# HT62N_v1_1.net
KiCad netlist of a schematic drawn in Altium Designer
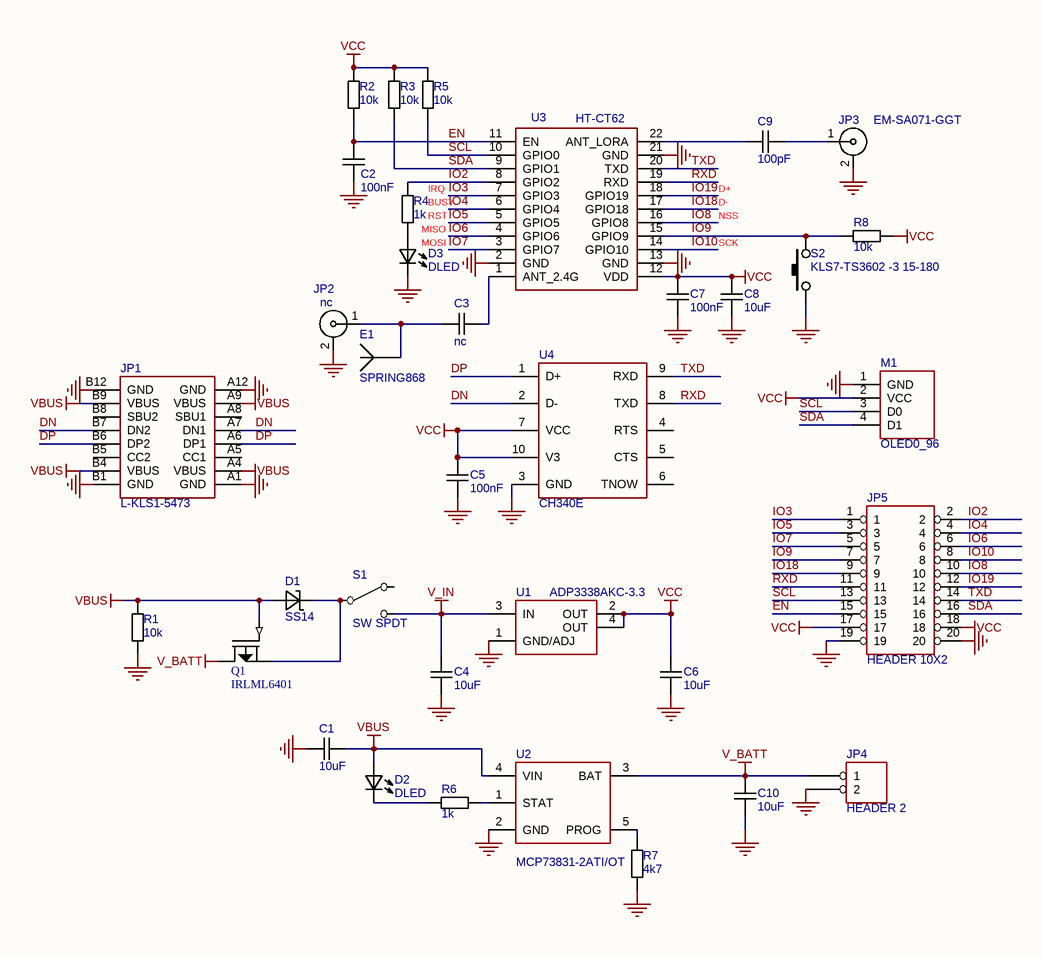
[diagram p0: HT62N_v1.1.SchDoc]

(export (version "E")
  (design (tool "Eeschema 10.0.6"))
  (components
    (comp (ref "C1")
      (value "10uF")
      (footprint "C-0805")
      (fields (field (name "VOLTAGE") "50V"))
      (libsource (lib "Passive") (part "CAPN"))
    )
    (comp (ref "C2")
      (value "100nF")
      (footprint "C-0603")
      (fields (field (name "VOLTAGE") "50V"))
      (libsource (lib "Passive") (part "CAPN"))
    )
    (comp (ref "C3")
      (value "nc")
      (footprint "C-0603")
      (fields (field (name "VOLTAGE") "50V"))
      (libsource (lib "Passive") (part "CAPN"))
    )
    (comp (ref "C4")
      (value "10uF")
      (footprint "C-0805")
      (fields (field (name "VOLTAGE") "50V"))
      (libsource (lib "Passive") (part "CAPN"))
    )
    (comp (ref "C5")
      (value "100nF")
      (footprint "C-0603")
      (fields (field (name "VOLTAGE") "50V"))
      (libsource (lib "Passive") (part "CAPN"))
    )
    (comp (ref "C6")
      (value "10uF")
      (footprint "C-0805")
      (fields (field (name "VOLTAGE") "50V"))
      (libsource (lib "Passive") (part "CAPN"))
    )
    (comp (ref "C7")
      (value "100nF")
      (footprint "C-0603")
      (fields (field (name "VOLTAGE") "50V"))
      (libsource (lib "Passive") (part "CAPN"))
    )
    (comp (ref "C8")
      (value "10uF")
      (footprint "C-0805")
      (fields (field (name "VOLTAGE") "50V"))
      (libsource (lib "Passive") (part "CAPN"))
    )
    (comp (ref "C9")
      (value "100pF")
      (footprint "C-0603")
      (fields (field (name "VOLTAGE") "50V"))
      (libsource (lib "Passive") (part "CAPN"))
    )
    (comp (ref "C10")
      (value "10uF")
      (footprint "C-0805")
      (fields (field (name "VOLTAGE") "50V"))
      (libsource (lib "Passive") (part "CAPN"))
    )
    (comp (ref "D1") (value "SS14") (footprint "D-SMA") (libsource (lib "Diodes") (part "DIODSH")))
    (comp (ref "D2") (value "DLED") (footprint "LED_3mm_RED") (libsource (lib "Diodes") (part "DLED")))
    (comp (ref "D3") (value "DLED") (footprint "LED_3mm_RED") (libsource (lib "Diodes") (part "DLED")))
    (comp (ref "E1") (value "SPRING868") (footprint "ANT_H868_V") (libsource (lib "Passive") (part "ANT")))
    (comp (ref "JP1")
      (value "L-KLS1-5473")
      (footprint "USB_C_SMD_SLOT")
      (libsource (lib "Connectors") (part "L-KLS1-5473"))
    )
    (comp (ref "JP2")
      (value "nc")
      (footprint "SMA_F_EDGE")
      (description "SMA Female R/A PCB Mount")
      (libsource (lib "Connectors") (part "SMA"))
    )
    (comp (ref "JP3")
      (value "EM-SA071-GGT")
      (footprint "SMA_F_EDGE")
      (description "SMA Female R/A PCB Mount")
      (libsource (lib "Connectors") (part "SMA"))
    )
    (comp (ref "JP4")
      (value "HEADER 2")
      (footprint "PLS1-2")
      (libsource (lib "Connectors") (part "HEADER 2"))
    )
    (comp (ref "JP5")
      (value "HEADER 10X2")
      (footprint "PLS2_10")
      (libsource (lib "Connectors") (part "HEADER 10X2"))
    )
    (comp (ref "M1")
      (value "OLED0_96")
      (footprint "OLED096_I2C")
      (libsource (lib "RFmodules") (part "OLED0_96_I2C"))
    )
    (comp (ref "Q1") (value "IRLML6401") (footprint "SOT-23") (libsource (lib "Discrete") (part "MOSF-P")))
    (comp (ref "R1") (value "10k") (footprint "R-0603") (libsource (lib "") (part "RES_2")))
    (comp (ref "R2") (value "10k") (footprint "R-0603") (libsource (lib "") (part "RES_1")))
    (comp (ref "R3") (value "10k") (footprint "R-0603") (libsource (lib "") (part "RES_1")))
    (comp (ref "R4") (value "1k") (footprint "R-0603") (libsource (lib "") (part "RES_2")))
    (comp (ref "R5") (value "10k") (footprint "R-0603") (libsource (lib "") (part "RES_1")))
    (comp (ref "R6") (value "1k") (footprint "R-0603") (libsource (lib "Passive") (part "RES")))
    (comp (ref "R7") (value "4k7") (footprint "R-0603") (libsource (lib "") (part "RES_2")))
    (comp (ref "R8") (value "10k") (footprint "R-0603") (libsource (lib "Passive") (part "RES")))
    (comp (ref "S1")
      (value "SW SPDT")
      (footprint "SK-12D07VG5")
      (libsource (lib "Switches") (part "SW SPDT"))
    )
    (comp (ref "S2")
      (value "KLS7-TS3602 -3 15-180")
      (footprint "KLS7-TS3602")
      (libsource (lib "Switches") (part "SW-1"))
    )
    (comp (ref "U1")
      (value "ADP3338AKC-3.3")
      (footprint "SOT223")
      (description "LOW CURRENT ADJUSTABLE  VOLTAGE REGULATOR")
      (libsource (lib "ICs") (part "LDL1117"))
    )
    (comp (ref "U2")
      (value "MCP73831-2ATI/OT")
      (footprint "SOT-23-5")
      (fields
        (field (name "LIBRARY PART") "IC`s.SchLib")
        (field (name "FOOTPRINT PART") "IC-package.PcbLib")
        (field (name "MANUFACTURER") "Texas Instruments")
      )
      (libsource (lib "ICs") (part "MCP73831-2ATI/OT"))
    )
    (comp (ref "U3") (value "HT-CT62") (footprint "HT-CT62") (libsource (lib "RFmodules") (part "HT-CT62")))
    (comp (ref "U4") (value "CH340E") (footprint "MSOP-10") (libsource (lib "ICs") (part "CH340E")))
  )
  (nets
    (net (code "1") (name "/DN") (class "Default")
      (node (ref "JP1") (pin "A7") (pinfunction "DN1_A7") (pintype "passive"))
      (node (ref "JP1") (pin "B7") (pinfunction "DN2_B7") (pintype "passive"))
      (node (ref "U4") (pin "2") (pinfunction "D-_2") (pintype "passive"))
    )
    (net (code "2") (name "/DP") (class "Default")
      (node (ref "JP1") (pin "A6") (pinfunction "DP1_A6") (pintype "passive"))
      (node (ref "JP1") (pin "B6") (pinfunction "DP2_B6") (pintype "passive"))
      (node (ref "U4") (pin "1") (pinfunction "D+_1") (pintype "passive"))
    )
    (net (code "3") (name "/EN") (class "Default")
      (node (ref "C2") (pin "2") (pinfunction "2_2") (pintype "passive"))
      (node (ref "JP5") (pin "15") (pinfunction "15_15") (pintype "passive"))
      (node (ref "R2") (pin "2") (pinfunction "2_2") (pintype "passive"))
      (node (ref "U3") (pin "11") (pinfunction "EN_11") (pintype "passive"))
    )
    (net (code "4") (name "/IO2") (class "Default")
      (node (ref "JP5") (pin "2") (pinfunction "2_2") (pintype "passive"))
      (node (ref "R4") (pin "2") (pinfunction "2_2") (pintype "passive"))
      (node (ref "U3") (pin "8") (pinfunction "GPIO2_8") (pintype "passive"))
    )
    (net (code "5") (name "/IO3") (class "Default")
      (node (ref "JP5") (pin "1") (pinfunction "1_1") (pintype "passive"))
      (node (ref "U3") (pin "7") (pinfunction "GPIO3_7") (pintype "passive"))
    )
    (net (code "6") (name "/IO4") (class "Default")
      (node (ref "JP5") (pin "4") (pinfunction "4_4") (pintype "passive"))
      (node (ref "U3") (pin "6") (pinfunction "GPIO4_6") (pintype "passive"))
    )
    (net (code "7") (name "/IO5") (class "Default")
      (node (ref "JP5") (pin "3") (pinfunction "3_3") (pintype "passive"))
      (node (ref "U3") (pin "5") (pinfunction "GPIO5_5") (pintype "passive"))
    )
    (net (code "8") (name "/IO6") (class "Default")
      (node (ref "JP5") (pin "6") (pinfunction "6_6") (pintype "passive"))
      (node (ref "U3") (pin "4") (pinfunction "GPIO6_4") (pintype "passive"))
    )
    (net (code "9") (name "/IO7") (class "Default")
      (node (ref "JP5") (pin "5") (pinfunction "5_5") (pintype "passive"))
      (node (ref "U3") (pin "3") (pinfunction "GPIO7_3") (pintype "passive"))
    )
    (net (code "10") (name "/IO8") (class "Default")
      (node (ref "JP5") (pin "10") (pinfunction "10_10") (pintype "passive"))
      (node (ref "U3") (pin "16") (pinfunction "GPIO8_16") (pintype "passive"))
    )
    (net (code "11") (name "/IO9") (class "Default")
      (node (ref "JP5") (pin "7") (pinfunction "7_7") (pintype "passive"))
      (node (ref "R8") (pin "2") (pinfunction "2_2") (pintype "passive"))
      (node (ref "S2") (pin "2") (pinfunction "2_2") (pintype "passive"))
      (node (ref "U3") (pin "15") (pinfunction "GPIO9_15") (pintype "passive"))
    )
    (net (code "12") (name "/IO10") (class "Default")
      (node (ref "JP5") (pin "8") (pinfunction "8_8") (pintype "passive"))
      (node (ref "U3") (pin "14") (pinfunction "GPIO10_14") (pintype "passive"))
    )
    (net (code "13") (name "/IO18") (class "Default")
      (node (ref "JP5") (pin "9") (pinfunction "9_9") (pintype "passive"))
      (node (ref "U3") (pin "17") (pinfunction "GPIO18_17") (pintype "passive"))
    )
    (net (code "14") (name "/IO19") (class "Default")
      (node (ref "JP5") (pin "12") (pinfunction "12_12") (pintype "passive"))
      (node (ref "U3") (pin "18") (pinfunction "GPIO19_18") (pintype "passive"))
    )
    (net (code "15") (name "/RXD") (class "Default")
      (node (ref "JP5") (pin "11") (pinfunction "11_11") (pintype "passive"))
      (node (ref "U3") (pin "19") (pinfunction "RXD_19") (pintype "passive"))
      (node (ref "U4") (pin "8") (pinfunction "TXD_8") (pintype "passive"))
    )
    (net (code "16") (name "/SCL") (class "Default")
      (node (ref "JP5") (pin "13") (pinfunction "13_13") (pintype "passive"))
      (node (ref "M1") (pin "3") (pinfunction "D0_3") (pintype "passive"))
      (node (ref "R5") (pin "2") (pinfunction "2_2") (pintype "passive"))
      (node (ref "U3") (pin "10") (pinfunction "GPIO0_10") (pintype "passive"))
    )
    (net (code "17") (name "/SDA") (class "Default")
      (node (ref "JP5") (pin "16") (pinfunction "16_16") (pintype "passive"))
      (node (ref "M1") (pin "4") (pinfunction "D1_4") (pintype "passive"))
      (node (ref "R3") (pin "2") (pinfunction "2_2") (pintype "passive"))
      (node (ref "U3") (pin "9") (pinfunction "GPIO1_9") (pintype "passive"))
    )
    (net (code "18") (name "/TXD") (class "Default")
      (node (ref "JP5") (pin "14") (pinfunction "14_14") (pintype "passive"))
      (node (ref "U3") (pin "20") (pinfunction "TXD_20") (pintype "passive"))
      (node (ref "U4") (pin "9") (pinfunction "RXD_9") (pintype "passive"))
    )
    (net (code "19") (name "GND") (class "Default")
      (node (ref "C1") (pin "1") (pinfunction "1_1") (pintype "passive"))
      (node (ref "C10") (pin "1") (pinfunction "1_1") (pintype "passive"))
      (node (ref "C2") (pin "1") (pinfunction "1_1") (pintype "passive"))
      (node (ref "C4") (pin "2") (pinfunction "2_2") (pintype "passive"))
      (node (ref "C5") (pin "1") (pinfunction "1_1") (pintype "passive"))
      (node (ref "C6") (pin "2") (pinfunction "2_2") (pintype "passive"))
      (node (ref "C7") (pin "1") (pinfunction "1_1") (pintype "passive"))
      (node (ref "C8") (pin "2") (pinfunction "2_2") (pintype "passive"))
      (node (ref "D3") (pin "2") (pinfunction "2_2") (pintype "passive"))
      (node (ref "JP1") (pin "A1") (pinfunction "GND_A1") (pintype "passive"))
      (node (ref "JP1") (pin "A12") (pinfunction "GND_A12") (pintype "passive"))
      (node (ref "JP1") (pin "B1") (pinfunction "GND_B1") (pintype "passive"))
      (node (ref "JP1") (pin "B12") (pinfunction "GND_B12") (pintype "passive"))
      (node (ref "JP2") (pin "2") (pinfunction "2_2") (pintype "passive"))
      (node (ref "JP3") (pin "2") (pinfunction "2_2") (pintype "passive"))
      (node (ref "JP4") (pin "2") (pinfunction "2_2") (pintype "passive"))
      (node (ref "JP5") (pin "19") (pinfunction "19_19") (pintype "passive"))
      (node (ref "JP5") (pin "20") (pinfunction "20_20") (pintype "passive"))
      (node (ref "M1") (pin "1") (pinfunction "GND_1") (pintype "passive"))
      (node (ref "R1") (pin "1") (pinfunction "1_1") (pintype "passive"))
      (node (ref "R7") (pin "1") (pinfunction "1_1") (pintype "passive"))
      (node (ref "S2") (pin "1") (pinfunction "1_1") (pintype "passive"))
      (node (ref "U1") (pin "1") (pinfunction "GND/ADJ_1") (pintype "power_in"))
      (node (ref "U2") (pin "2") (pinfunction "GND_2") (pintype "passive"))
      (node (ref "U3") (pin "13") (pinfunction "GND_13") (pintype "passive"))
      (node (ref "U3") (pin "2") (pinfunction "GND_2") (pintype "passive"))
      (node (ref "U3") (pin "21") (pinfunction "GND_21") (pintype "passive"))
      (node (ref "U4") (pin "3") (pinfunction "GND_3") (pintype "passive"))
    )
    (net (code "20") (name "Net-(C3-Pad1)") (class "Default")
      (node (ref "C3") (pin "1") (pinfunction "1_1") (pintype "passive"))
      (node (ref "E1") (pin "1") (pinfunction "1_1") (pintype "passive"))
      (node (ref "JP2") (pin "1") (pinfunction "1_1") (pintype "passive"))
    )
    (net (code "21") (name "Net-(C9-Pad2)") (class "Default")
      (node (ref "C9") (pin "2") (pinfunction "2_2") (pintype "passive"))
      (node (ref "JP3") (pin "1") (pinfunction "1_1") (pintype "passive"))
    )
    (net (code "22") (name "Net-(D2-Pad2)") (class "Default")
      (node (ref "D2") (pin "2") (pinfunction "2_2") (pintype "passive"))
      (node (ref "R6") (pin "2") (pinfunction "2_2") (pintype "passive"))
    )
    (net (code "23") (name "Net-(D3-Pad1)") (class "Default")
      (node (ref "D3") (pin "1") (pinfunction "1_1") (pintype "passive"))
      (node (ref "R4") (pin "1") (pinfunction "1_1") (pintype "passive"))
    )
    (net (code "24") (name "Net-(Q1-SOURCE)") (class "Default")
      (node (ref "D1") (pin "2") (pinfunction "2_2") (pintype "passive"))
      (node (ref "Q1") (pin "2") (pinfunction "SOURCE_2") (pintype "passive"))
      (node (ref "S1") (pin "2") (pinfunction "COMMON_2") (pintype "passive"))
    )
    (net (code "25") (name "Net-(U2-PROG)") (class "Default")
      (node (ref "R7") (pin "2") (pinfunction "2_2") (pintype "passive"))
      (node (ref "U2") (pin "5") (pinfunction "PROG_5") (pintype "passive"))
    )
    (net (code "26") (name "Net-(U2-STAT)") (class "Default")
      (node (ref "R6") (pin "1") (pinfunction "1_1") (pintype "passive"))
      (node (ref "U2") (pin "1") (pinfunction "STAT_1") (pintype "passive"))
    )
    (net (code "27") (name "Net-(U3-ANT_2.4G)") (class "Default")
      (node (ref "C3") (pin "2") (pinfunction "2_2") (pintype "passive"))
      (node (ref "U3") (pin "1") (pinfunction "ANT_2.4G_1") (pintype "passive"))
    )
    (net (code "28") (name "Net-(U3-ANT_LORA)") (class "Default")
      (node (ref "C9") (pin "1") (pinfunction "1_1") (pintype "passive"))
      (node (ref "U3") (pin "22") (pinfunction "ANT_LORA_22") (pintype "passive"))
    )
    (net (code "29") (name "VBUS") (class "Default")
      (node (ref "C1") (pin "2") (pinfunction "2_2") (pintype "passive"))
      (node (ref "D1") (pin "1") (pinfunction "1_1") (pintype "passive"))
      (node (ref "D2") (pin "1") (pinfunction "1_1") (pintype "passive"))
      (node (ref "JP1") (pin "A4") (pinfunction "VBUS_A4") (pintype "passive"))
      (node (ref "JP1") (pin "A9") (pinfunction "VBUS_A9") (pintype "passive"))
      (node (ref "JP1") (pin "B4") (pinfunction "VBUS_B4") (pintype "passive"))
      (node (ref "JP1") (pin "B9") (pinfunction "VBUS_B9") (pintype "passive"))
      (node (ref "Q1") (pin "1") (pinfunction "GATE_1") (pintype "input"))
      (node (ref "R1") (pin "2") (pinfunction "2_2") (pintype "passive"))
      (node (ref "U2") (pin "4") (pinfunction "VIN_4") (pintype "passive"))
    )
    (net (code "30") (name "VCC") (class "Default")
      (node (ref "C5") (pin "2") (pinfunction "2_2") (pintype "passive"))
      (node (ref "C6") (pin "1") (pinfunction "1_1") (pintype "passive"))
      (node (ref "C7") (pin "2") (pinfunction "2_2") (pintype "passive"))
      (node (ref "C8") (pin "1") (pinfunction "1_1") (pintype "passive"))
      (node (ref "JP5") (pin "17") (pinfunction "17_17") (pintype "passive"))
      (node (ref "JP5") (pin "18") (pinfunction "18_18") (pintype "passive"))
      (node (ref "M1") (pin "2") (pinfunction "VCC_2") (pintype "passive"))
      (node (ref "R2") (pin "1") (pinfunction "1_1") (pintype "passive"))
      (node (ref "R3") (pin "1") (pinfunction "1_1") (pintype "passive"))
      (node (ref "R5") (pin "1") (pinfunction "1_1") (pintype "passive"))
      (node (ref "R8") (pin "1") (pinfunction "1_1") (pintype "passive"))
      (node (ref "U1") (pin "2") (pinfunction "OUT_2") (pintype "power_in"))
      (node (ref "U1") (pin "4") (pinfunction "OUT_4") (pintype "power_in"))
      (node (ref "U3") (pin "12") (pinfunction "VDD_12") (pintype "passive"))
      (node (ref "U4") (pin "10") (pinfunction "V3_10") (pintype "passive"))
      (node (ref "U4") (pin "7") (pinfunction "VCC_7") (pintype "passive"))
    )
    (net (code "31") (name "VSS") (class "Default")
      (node (ref "JP1") (pin "17") (pinfunction "VSS_17") (pintype "power_in"))
    )
    (net (code "32") (name "V_BATT") (class "Default")
      (node (ref "C10") (pin "2") (pinfunction "2_2") (pintype "passive"))
      (node (ref "JP4") (pin "1") (pinfunction "1_1") (pintype "passive"))
      (node (ref "Q1") (pin "3") (pinfunction "DRAIN_3") (pintype "passive"))
      (node (ref "U2") (pin "3") (pinfunction "BAT_3") (pintype "passive"))
    )
    (net (code "33") (name "V_IN") (class "Default")
      (node (ref "C4") (pin "1") (pinfunction "1_1") (pintype "passive"))
      (node (ref "S1") (pin "3") (pinfunction "NO_3") (pintype "passive"))
      (node (ref "U1") (pin "3") (pinfunction "IN_3") (pintype "power_in"))
    )
    (net (code "34") (name "unconnected-(JP1-CC1-PadA5)") (class "Default")
      (node (ref "JP1") (pin "A5") (pinfunction "CC1_A5") (pintype "passive"))
    )
    (net (code "35") (name "unconnected-(JP1-CC2-PadB5)") (class "Default")
      (node (ref "JP1") (pin "B5") (pinfunction "CC2_B5") (pintype "passive"))
    )
    (net (code "36") (name "unconnected-(JP1-SBU1-PadA8)") (class "Default")
      (node (ref "JP1") (pin "A8") (pinfunction "SBU1_A8") (pintype "passive"))
    )
    (net (code "37") (name "unconnected-(JP1-SBU2-PadB8)") (class "Default")
      (node (ref "JP1") (pin "B8") (pinfunction "SBU2_B8") (pintype "passive"))
    )
    (net (code "38") (name "unconnected-(S1-NC-Pad1)") (class "Default")
      (node (ref "S1") (pin "1") (pinfunction "NC_1") (pintype "passive"))
    )
    (net (code "39") (name "unconnected-(U4-CTS-Pad5)") (class "Default")
      (node (ref "U4") (pin "5") (pinfunction "CTS_5") (pintype "passive"))
    )
    (net (code "40") (name "unconnected-(U4-RTS-Pad4)") (class "Default")
      (node (ref "U4") (pin "4") (pinfunction "RTS_4") (pintype "passive"))
    )
    (net (code "41") (name "unconnected-(U4-TNOW-Pad6)") (class "Default")
      (node (ref "U4") (pin "6") (pinfunction "TNOW_6") (pintype "passive"))
    )
  )
)
